# medusa-ai-sensors.net
KiCad netlist of a schematic drawn in Altium Designer
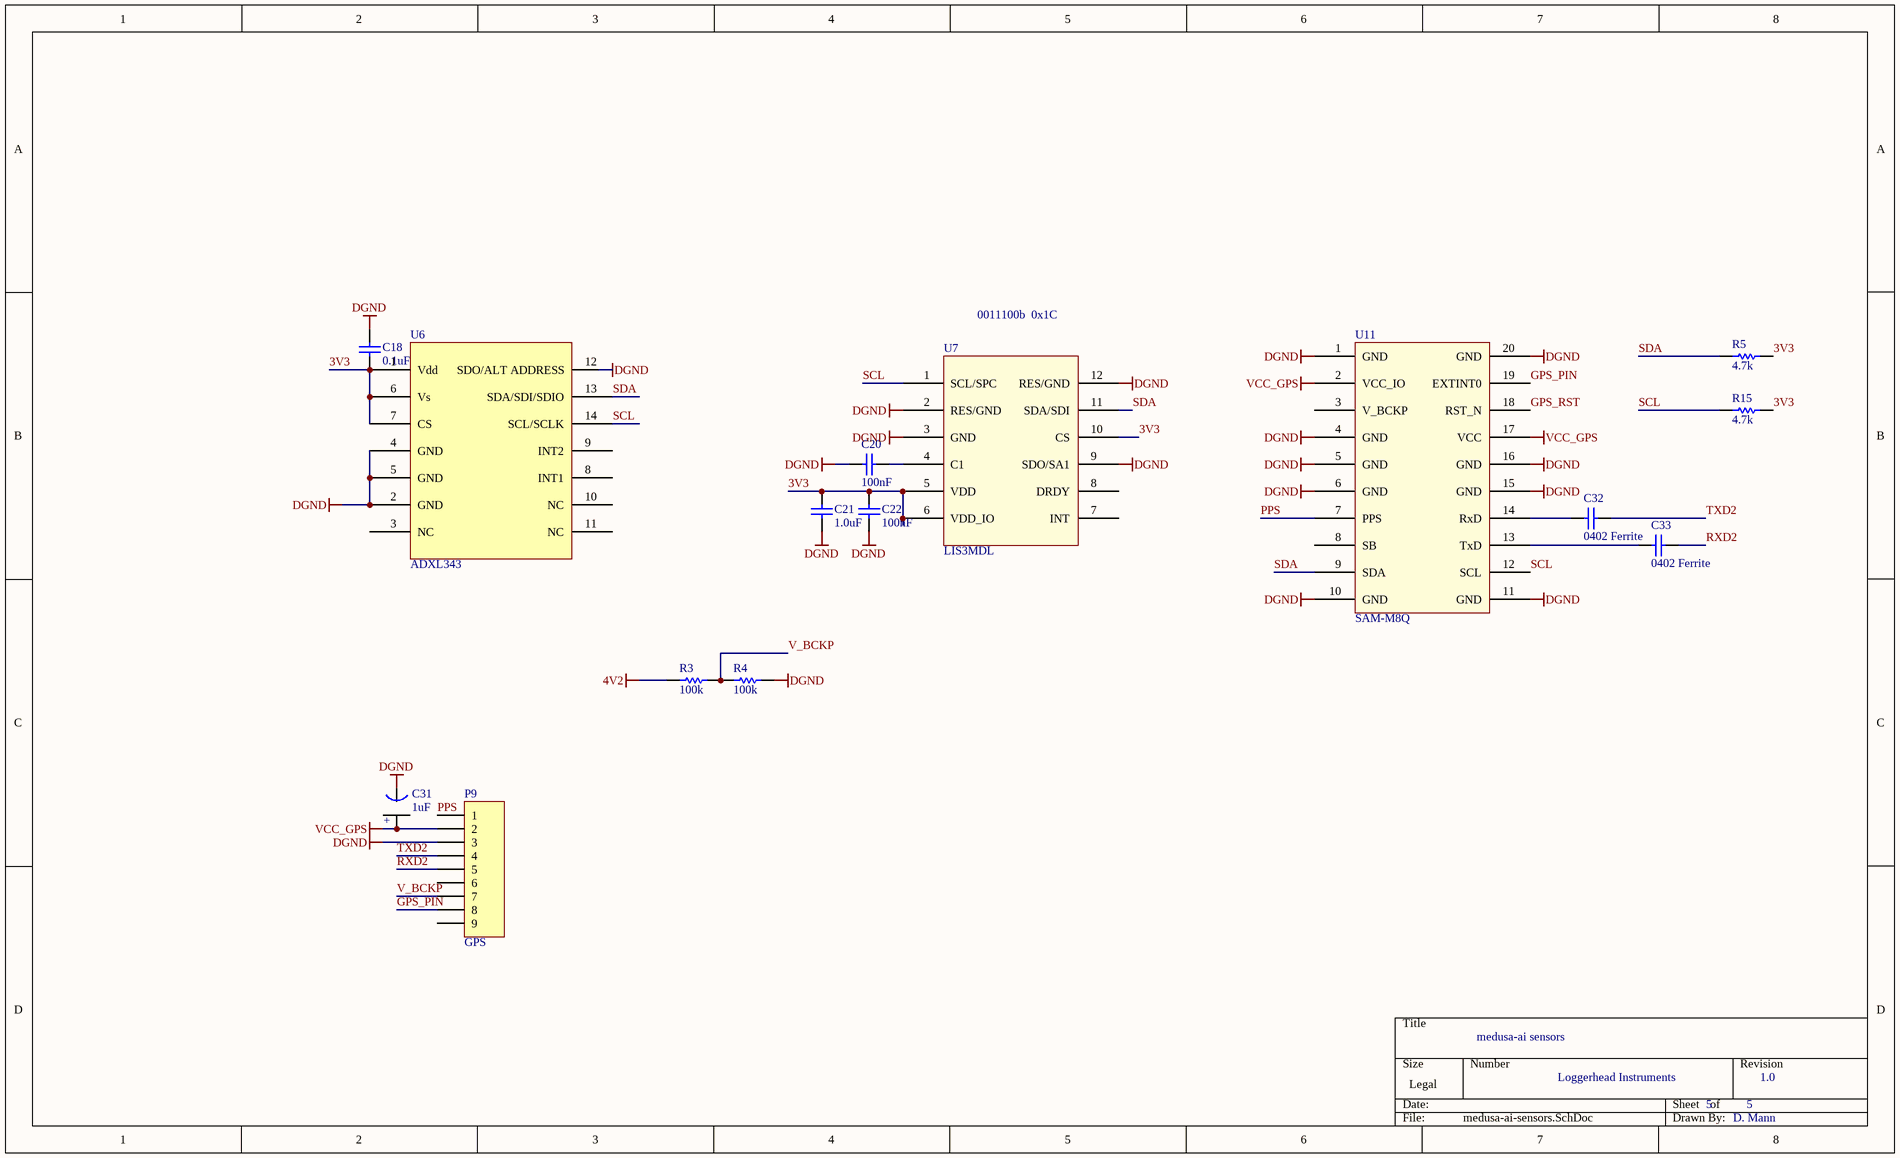
[diagram p0: medusa-ai-sensors.SchDoc]

(export (version "E")
  (design (tool "Eeschema 10.0.6"))
  (components
    (comp (ref "C18")
      (value "0.1uF")
      (footprint "0402")
      (description "Ceramic Chip Capacitor - Standard")
      (fields (field (name "PUBLISHER") "Altium Limited"))
      (libsource (lib "KEMET Chip Capacitor") (part "C0402"))
    )
    (comp (ref "C20")
      (value "100nF")
      (footprint "0402")
      (description "Ceramic Chip Capacitor - Standard")
      (fields (field (name "PUBLISHER") "Altium Limited"))
      (libsource (lib "KEMET Chip Capacitor") (part "C0402"))
    )
    (comp (ref "C21")
      (value "1.0uF")
      (footprint "0402")
      (description "Ceramic Chip Capacitor - Standard")
      (fields (field (name "PUBLISHER") "Altium Limited"))
      (libsource (lib "KEMET Chip Capacitor") (part "C0402"))
    )
    (comp (ref "C22")
      (value "100nF")
      (footprint "0402")
      (description "Ceramic Chip Capacitor - Standard")
      (fields (field (name "PUBLISHER") "Altium Limited"))
      (libsource (lib "KEMET Chip Capacitor") (part "C0402"))
    )
    (comp (ref "C31") (value "1uF") (footprint "Tant0805") (libsource (lib "Loggerhead") (part "Tant0805")))
    (comp (ref "C32")
      (value "0402 Ferrite")
      (footprint "0402")
      (description "Ceramic Chip Capacitor - Standard")
      (fields (field (name "PUBLISHER") "Altium Limited"))
      (libsource (lib "KEMET Chip Capacitor") (part "C0402"))
    )
    (comp (ref "C33")
      (value "0402 Ferrite")
      (footprint "0402")
      (description "Ceramic Chip Capacitor - Standard")
      (fields (field (name "PUBLISHER") "Altium Limited"))
      (libsource (lib "KEMET Chip Capacitor") (part "C0402"))
    )
    (comp (ref "P9")
      (value "GPS")
      (footprint "HDR1X9")
      (description "Header, 9-Pin")
      (fields (field (name "PUBLISHER") "Altium Limited"))
      (libsource (lib "Miscellaneous Connectors") (part "Header 9"))
    )
    (comp (ref "R3")
      (value "100k")
      (footprint "3-0603")
      (fields (field (name "PUBLISHER") "Altium Limited"))
      (libsource (lib "Panasonic Resistor") (part "ERJ3RK"))
    )
    (comp (ref "R4")
      (value "100k")
      (footprint "3-0603")
      (fields (field (name "PUBLISHER") "Altium Limited"))
      (libsource (lib "Panasonic Resistor") (part "ERJ3RK"))
    )
    (comp (ref "R5")
      (value "4.7k")
      (footprint "3-0603")
      (fields (field (name "PUBLISHER") "Altium Limited"))
      (libsource (lib "Panasonic Resistor") (part "ERJ3RK"))
    )
    (comp (ref "R15")
      (value "4.7k")
      (footprint "3-0603")
      (fields (field (name "PUBLISHER") "Altium Limited"))
      (libsource (lib "Panasonic Resistor") (part "ERJ3RK"))
    )
    (comp (ref "U6") (value "ADXL343") (footprint "ADXL345") (libsource (lib "Loggerhead") (part "ADXL345")))
    (comp (ref "U7")
      (value "LIS3MDL")
      (footprint "LGA-12")
      (description "magnetometer")
      (libsource (lib "Loggerhead") (part "LIS3MDL"))
    )
    (comp (ref "U11")
      (value "SAM-M8Q")
      (footprint "GPS SAM-MQ8")
      (libsource (lib "Loggerhead") (part "GPS SAM-M8Q"))
    )
  )
  (nets
    (net (code "1") (name "/3V3") (class "Default")
      (node (ref "C18") (pin "1") (pinfunction "1_1") (pintype "passive"))
      (node (ref "C21") (pin "1") (pinfunction "1_1") (pintype "passive"))
      (node (ref "C22") (pin "1") (pinfunction "1_1") (pintype "passive"))
      (node (ref "R15") (pin "2") (pinfunction "2_2") (pintype "passive"))
      (node (ref "R5") (pin "2") (pinfunction "2_2") (pintype "passive"))
      (node (ref "U6") (pin "1") (pinfunction "Vdd_1") (pintype "power_in"))
      (node (ref "U6") (pin "6") (pinfunction "Vs_6") (pintype "passive"))
      (node (ref "U6") (pin "7") (pinfunction "CS_7") (pintype "passive"))
      (node (ref "U7") (pin "10") (pinfunction "CS_10") (pintype "passive"))
      (node (ref "U7") (pin "5") (pinfunction "VDD_5") (pintype "passive"))
      (node (ref "U7") (pin "6") (pinfunction "VDD_IO_6") (pintype "passive"))
    )
    (net (code "2") (name "/GPS_PIN") (class "Default")
      (node (ref "P9") (pin "8") (pinfunction "8_8") (pintype "passive"))
      (node (ref "U11") (pin "19") (pinfunction "EXTINT0_19") (pintype "passive"))
    )
    (net (code "3") (name "/GPS_RST") (class "Default")
      (node (ref "U11") (pin "18") (pinfunction "RST_N_18") (pintype "passive"))
    )
    (net (code "4") (name "/PPS") (class "Default")
      (node (ref "P9") (pin "1") (pinfunction "1_1") (pintype "passive"))
      (node (ref "U11") (pin "7") (pinfunction "PPS_7") (pintype "passive"))
    )
    (net (code "5") (name "/RXD2") (class "Default")
      (node (ref "C33") (pin "2") (pinfunction "2_2") (pintype "passive"))
      (node (ref "P9") (pin "5") (pinfunction "5_5") (pintype "passive"))
    )
    (net (code "6") (name "/SCL") (class "Default")
      (node (ref "R15") (pin "1") (pinfunction "1_1") (pintype "passive"))
      (node (ref "U11") (pin "12") (pinfunction "SCL_12") (pintype "passive"))
      (node (ref "U6") (pin "14") (pinfunction "SCL/SCLK_14") (pintype "passive"))
      (node (ref "U7") (pin "1") (pinfunction "SCL/SPC_1") (pintype "passive"))
    )
    (net (code "7") (name "/SDA") (class "Default")
      (node (ref "R5") (pin "1") (pinfunction "1_1") (pintype "passive"))
      (node (ref "U11") (pin "9") (pinfunction "SDA_9") (pintype "passive"))
      (node (ref "U6") (pin "13") (pinfunction "SDA/SDI/SDIO_13") (pintype "passive"))
      (node (ref "U7") (pin "11") (pinfunction "SDA/SDI_11") (pintype "passive"))
    )
    (net (code "8") (name "/TXD2") (class "Default")
      (node (ref "C32") (pin "2") (pinfunction "2_2") (pintype "passive"))
      (node (ref "P9") (pin "4") (pinfunction "4_4") (pintype "passive"))
    )
    (net (code "9") (name "/V_BCKP") (class "Default")
      (node (ref "P9") (pin "7") (pinfunction "7_7") (pintype "passive"))
      (node (ref "R3") (pin "1") (pinfunction "1_1") (pintype "passive"))
      (node (ref "R4") (pin "2") (pinfunction "2_2") (pintype "passive"))
    )
    (net (code "10") (name "4V2") (class "Default")
      (node (ref "R3") (pin "2") (pinfunction "2_2") (pintype "passive"))
    )
    (net (code "11") (name "DGND") (class "Default")
      (node (ref "C18") (pin "2") (pinfunction "2_2") (pintype "passive"))
      (node (ref "C20") (pin "1") (pinfunction "1_1") (pintype "passive"))
      (node (ref "C21") (pin "2") (pinfunction "2_2") (pintype "passive"))
      (node (ref "C22") (pin "2") (pinfunction "2_2") (pintype "passive"))
      (node (ref "C31") (pin "1") (pinfunction "GND_1") (pintype "passive"))
      (node (ref "P9") (pin "3") (pinfunction "3_3") (pintype "passive"))
      (node (ref "R4") (pin "1") (pinfunction "1_1") (pintype "passive"))
      (node (ref "U11") (pin "1") (pinfunction "GND_1") (pintype "passive"))
      (node (ref "U11") (pin "10") (pinfunction "GND_10") (pintype "passive"))
      (node (ref "U11") (pin "11") (pinfunction "GND_11") (pintype "passive"))
      (node (ref "U11") (pin "15") (pinfunction "GND_15") (pintype "passive"))
      (node (ref "U11") (pin "16") (pinfunction "GND_16") (pintype "passive"))
      (node (ref "U11") (pin "20") (pinfunction "GND_20") (pintype "passive"))
      (node (ref "U11") (pin "4") (pinfunction "GND_4") (pintype "passive"))
      (node (ref "U11") (pin "5") (pinfunction "GND_5") (pintype "passive"))
      (node (ref "U11") (pin "6") (pinfunction "GND_6") (pintype "passive"))
      (node (ref "U6") (pin "12") (pinfunction "SDO/ALT_ADDRESS_12") (pintype "passive"))
      (node (ref "U6") (pin "2") (pinfunction "GND_2") (pintype "passive"))
      (node (ref "U6") (pin "4") (pinfunction "GND_4") (pintype "passive"))
      (node (ref "U6") (pin "5") (pinfunction "GND_5") (pintype "passive"))
      (node (ref "U7") (pin "12") (pinfunction "RES/GND_12") (pintype "passive"))
      (node (ref "U7") (pin "2") (pinfunction "RES/GND_2") (pintype "passive"))
      (node (ref "U7") (pin "3") (pinfunction "GND_3") (pintype "passive"))
      (node (ref "U7") (pin "9") (pinfunction "SDO/SA1_9") (pintype "passive"))
    )
    (net (code "12") (name "Net-(U7-C1)") (class "Default")
      (node (ref "C20") (pin "2") (pinfunction "2_2") (pintype "passive"))
      (node (ref "U7") (pin "4") (pinfunction "C1_4") (pintype "passive"))
    )
    (net (code "13") (name "Net-(U11-RxD)") (class "Default")
      (node (ref "C32") (pin "1") (pinfunction "1_1") (pintype "passive"))
      (node (ref "U11") (pin "14") (pinfunction "RxD_14") (pintype "passive"))
    )
    (net (code "14") (name "Net-(U11-TxD)") (class "Default")
      (node (ref "C33") (pin "1") (pinfunction "1_1") (pintype "passive"))
      (node (ref "U11") (pin "13") (pinfunction "TxD_13") (pintype "passive"))
    )
    (net (code "15") (name "VCC_GPS") (class "Default")
      (node (ref "C31") (pin "2") (pinfunction "+_2") (pintype "passive"))
      (node (ref "P9") (pin "2") (pinfunction "2_2") (pintype "passive"))
      (node (ref "U11") (pin "17") (pinfunction "VCC_17") (pintype "passive"))
      (node (ref "U11") (pin "2") (pinfunction "VCC_IO_2") (pintype "passive"))
    )
    (net (code "16") (name "unconnected-(P9-Pad6)") (class "Default")
      (node (ref "P9") (pin "6") (pinfunction "6_6") (pintype "passive"))
    )
    (net (code "17") (name "unconnected-(P9-Pad9)") (class "Default")
      (node (ref "P9") (pin "9") (pinfunction "9_9") (pintype "passive"))
    )
    (net (code "18") (name "unconnected-(U6-INT1-Pad8)") (class "Default")
      (node (ref "U6") (pin "8") (pinfunction "INT1_8") (pintype "passive"))
    )
    (net (code "19") (name "unconnected-(U6-INT2-Pad9)") (class "Default")
      (node (ref "U6") (pin "9") (pinfunction "INT2_9") (pintype "passive"))
    )
    (net (code "20") (name "unconnected-(U6-NC-Pad3)") (class "Default")
      (node (ref "U6") (pin "3") (pinfunction "NC_3") (pintype "passive"))
    )
    (net (code "21") (name "unconnected-(U6-NC-Pad10)") (class "Default")
      (node (ref "U6") (pin "10") (pinfunction "NC_10") (pintype "passive"))
    )
    (net (code "22") (name "unconnected-(U6-NC-Pad11)") (class "Default")
      (node (ref "U6") (pin "11") (pinfunction "NC_11") (pintype "passive"))
    )
    (net (code "23") (name "unconnected-(U7-DRDY-Pad8)") (class "Default")
      (node (ref "U7") (pin "8") (pinfunction "DRDY_8") (pintype "passive"))
    )
    (net (code "24") (name "unconnected-(U7-INT-Pad7)") (class "Default")
      (node (ref "U7") (pin "7") (pinfunction "INT_7") (pintype "passive"))
    )
    (net (code "25") (name "unconnected-(U11-SB-Pad8)") (class "Default")
      (node (ref "U11") (pin "8") (pinfunction "SB_8") (pintype "passive"))
    )
    (net (code "26") (name "unconnected-(U11-V_BCKP-Pad3)") (class "Default")
      (node (ref "U11") (pin "3") (pinfunction "V_BCKP_3") (pintype "passive"))
    )
  )
)
